# design.net
KiCad netlist of a schematic drawn in EasyEDA Pro
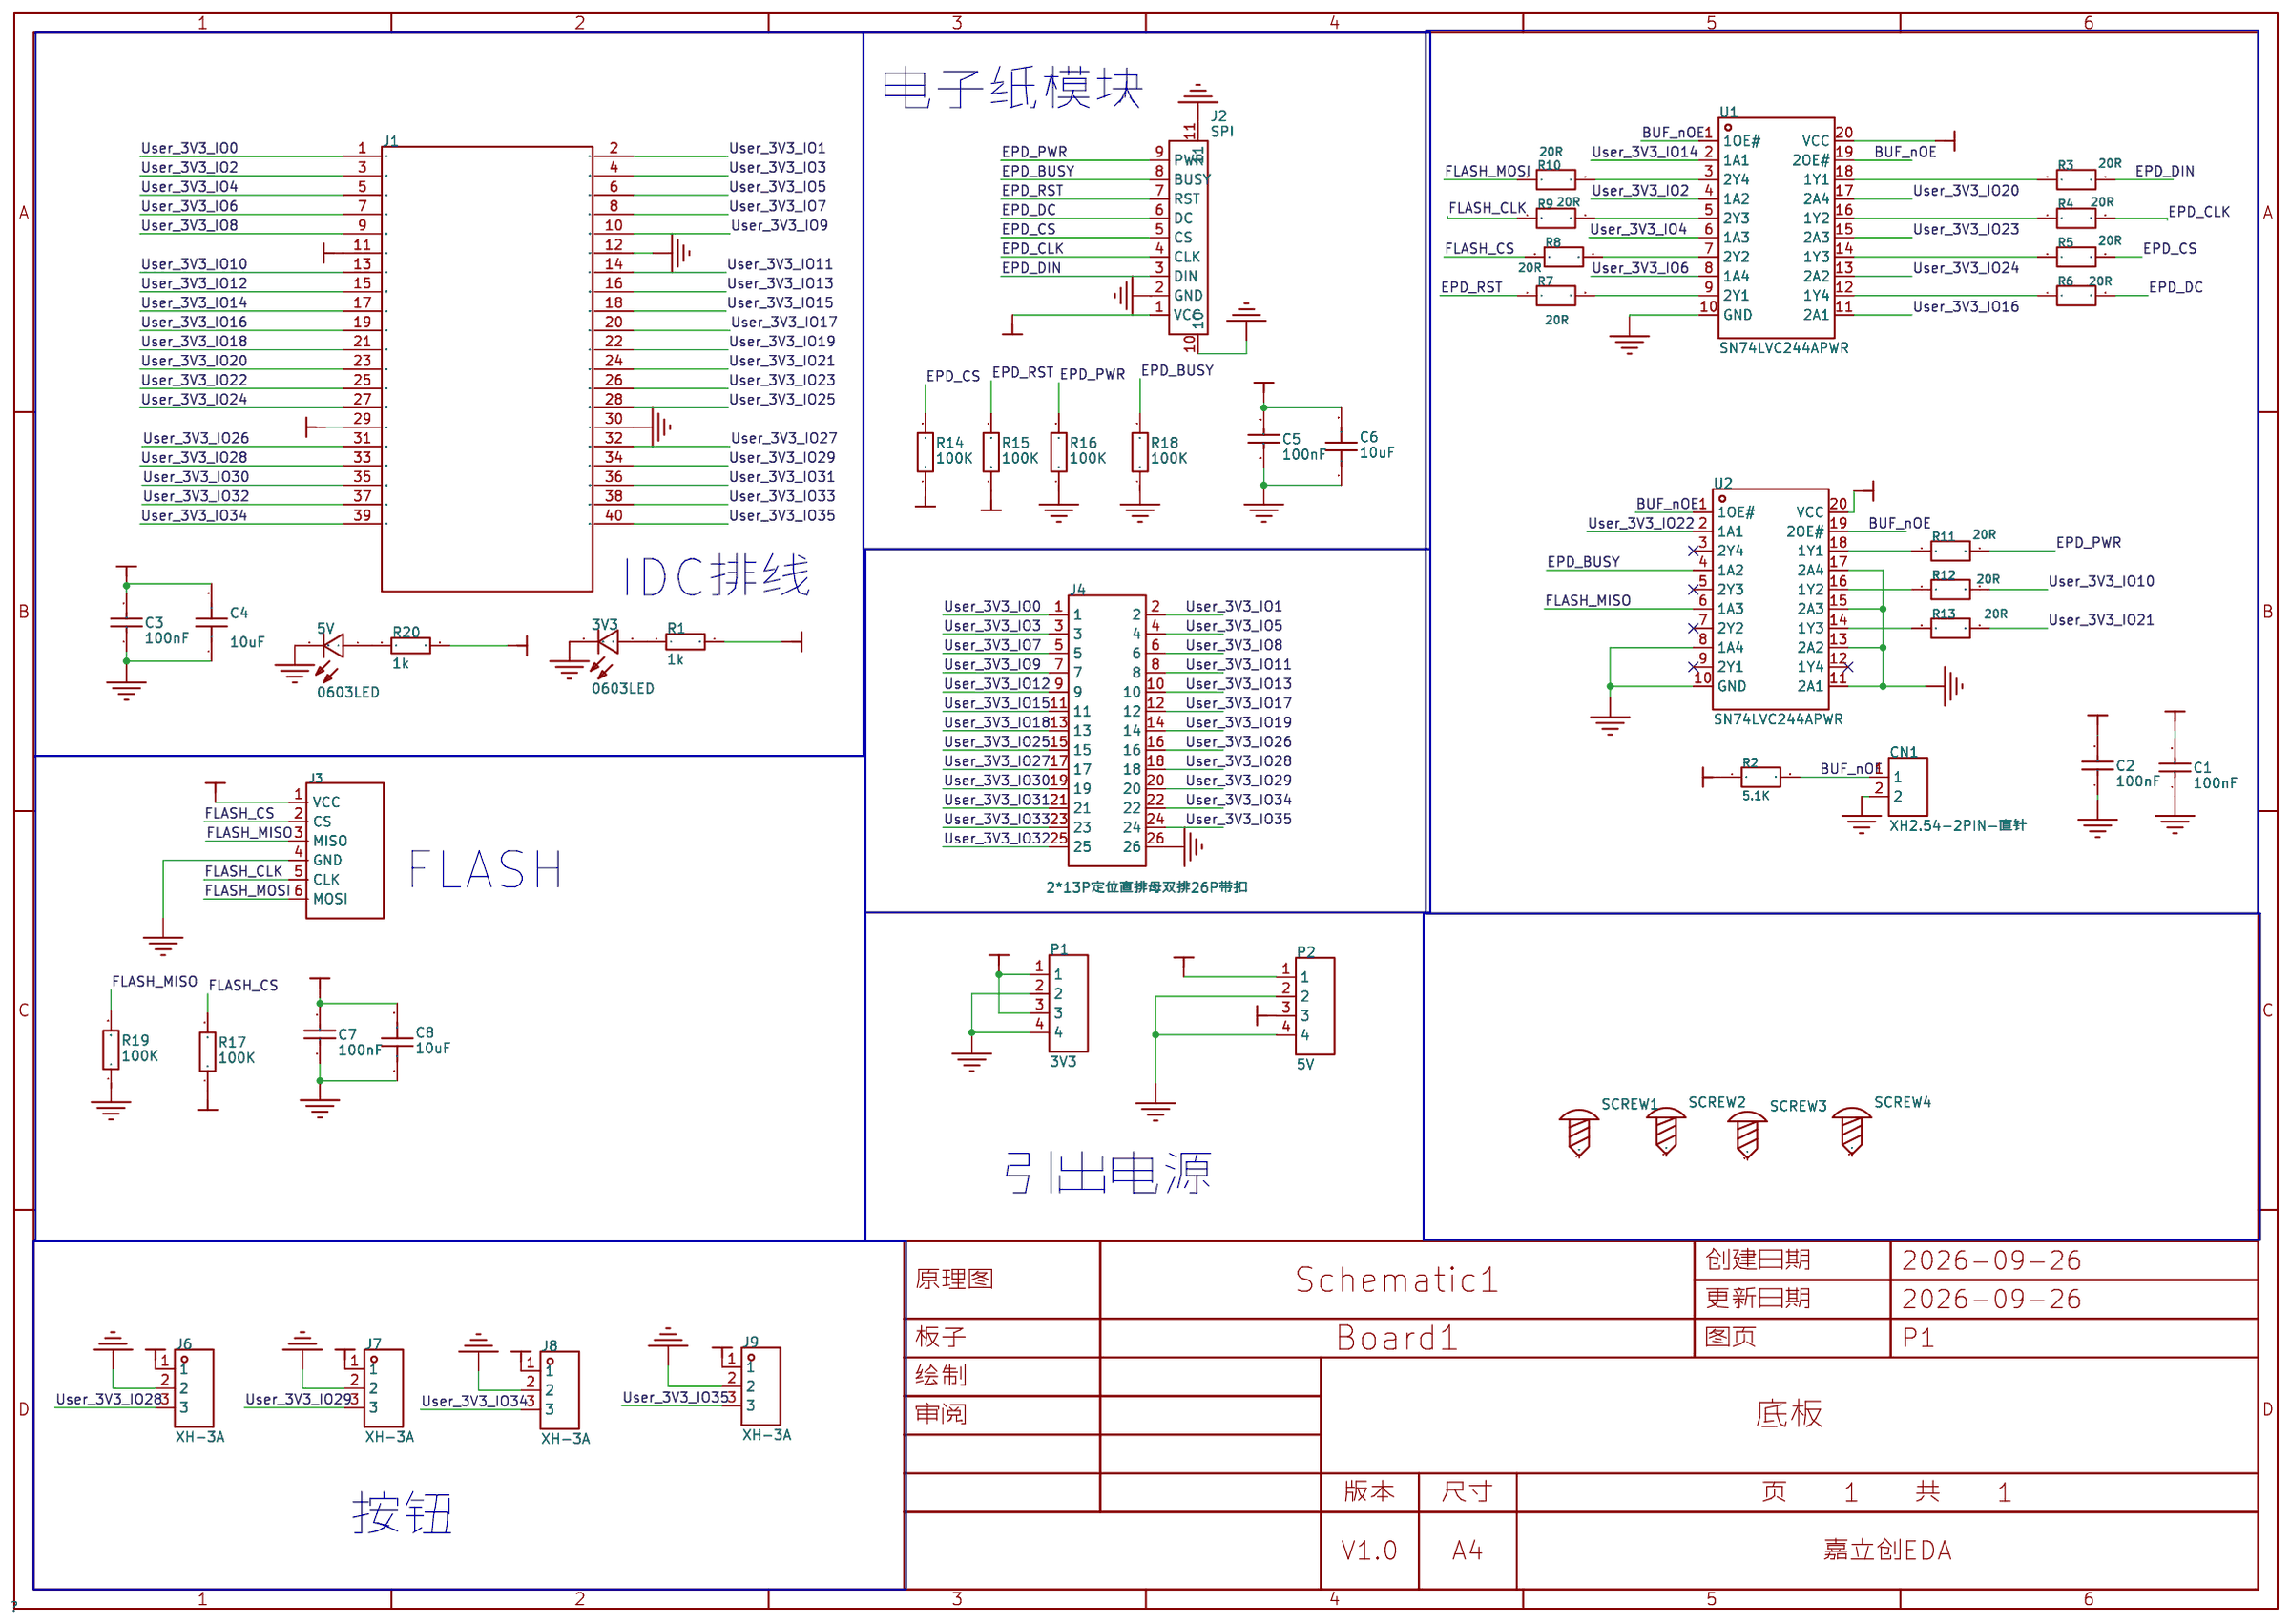
[diagram p0: schematic sheet]

(export (version "E")
  (design (tool "Eeschema 10.0.6"))
  (components
    (comp (ref "3V3")
      (value "0603LED")
      (footprint "easyedapro:LED0603-R-RD_RED")
      (libsource (lib "easyedapro") (part "0603LED"))
    )
    (comp (ref "5V")
      (value "0603LED")
      (footprint "easyedapro:LED0603-R-RD_RED")
      (libsource (lib "easyedapro") (part "0603LED"))
    )
    (comp (ref "C1")
      (value "100nF")
      (footprint "easyedapro:C0603")
      (fields
        (field (name "Manufacturer Part") "CL10A225KO8NNNC")
        (field (name "Manufacturer") "SAMSUNG(三星)")
      )
      (libsource (lib "easyedapro") (part "CL10A225KO8NNNC"))
    )
    (comp (ref "C2")
      (value "100nF")
      (footprint "easyedapro:C0603")
      (fields
        (field (name "Manufacturer Part") "CL10A225KO8NNNC")
        (field (name "Manufacturer") "SAMSUNG(三星)")
      )
      (libsource (lib "easyedapro") (part "CL10A225KO8NNNC"))
    )
    (comp (ref "C3")
      (value "100nF")
      (footprint "easyedapro:C0603")
      (fields
        (field (name "Manufacturer Part") "CL10A225KO8NNNC")
        (field (name "Manufacturer") "SAMSUNG(三星)")
      )
      (libsource (lib "easyedapro") (part "CL10A225KO8NNNC"))
    )
    (comp (ref "C4")
      (value "10uF")
      (footprint "easyedapro:C0805")
      (fields
        (field (name "Manufacturer Part") "GRM21BR61H106KE43L")
        (field (name "Manufacturer") "muRata(村田)")
      )
      (libsource (lib "easyedapro") (part "GRM21BR61H106KE43L"))
    )
    (comp (ref "C5")
      (value "100nF")
      (footprint "easyedapro:C0603")
      (fields
        (field (name "Manufacturer Part") "CL10A225KO8NNNC")
        (field (name "Manufacturer") "SAMSUNG(三星)")
      )
      (libsource (lib "easyedapro") (part "CL10A225KO8NNNC"))
    )
    (comp (ref "C6")
      (value "10uF")
      (footprint "easyedapro:C0805")
      (fields
        (field (name "Manufacturer Part") "GRM21BR61H106KE43L")
        (field (name "Manufacturer") "muRata(村田)")
      )
      (libsource (lib "easyedapro") (part "GRM21BR61H106KE43L"))
    )
    (comp (ref "C7")
      (value "100nF")
      (footprint "easyedapro:C0603")
      (fields
        (field (name "Manufacturer Part") "CL10A225KO8NNNC")
        (field (name "Manufacturer") "SAMSUNG(三星)")
      )
      (libsource (lib "easyedapro") (part "CL10A225KO8NNNC"))
    )
    (comp (ref "C8")
      (value "10uF")
      (footprint "easyedapro:C0805")
      (fields
        (field (name "Manufacturer Part") "GRM21BR61H106KE43L")
        (field (name "Manufacturer") "muRata(村田)")
      )
      (libsource (lib "easyedapro") (part "GRM21BR61H106KE43L"))
    )
    (comp (ref "CN1")
      (value "XH2.54-2PIN-直针")
      (footprint "easyedapro:CONN-TH_XH2.54-2P")
      (libsource (lib "easyedapro") (part "XH2.54-2PIN-直针"))
    )
    (comp (ref "J1")
      (value "~")
      (footprint "easyedapro:IDC40P")
      (libsource (lib "easyedapro") (part "iDC40P"))
    )
    (comp (ref "J2")
      (value "SPI")
      (footprint "easyedapro:CONN-SMD_9P-P1.25_BX-GH1.25-9PWT")
      (fields (field (name "Manufacturer") "Bossie(博锡)"))
      (libsource (lib "easyedapro") (part "BX-GH1.25-9PWT"))
    )
    (comp (ref "J3")
      (value "X4611FV-06-C63D28")
      (footprint "easyedapro:HDR-TH_6P-P2.00-V-F")
      (fields (field (name "Manufacturer") "XKB Connection(中国星坤)"))
      (libsource (lib "easyedapro") (part "X4611FV-06-C63D28"))
    )
    (comp (ref "J4")
      (value "2*13P定位直排母双排26P带扣")
      (footprint "easyedapro:IDC-TH_26P-P2.54-V-M-R2-C13-S2.54")
      (libsource (lib "easyedapro") (part "2*13P定位直排母双排26P带扣"))
    )
    (comp (ref "J6")
      (value "XH-3A")
      (footprint "easyedapro:CONN-TH_3P-P2.50_C9900023074")
      (libsource (lib "easyedapro") (part "XH-3A_C9900023074"))
    )
    (comp (ref "J7")
      (value "XH-3A")
      (footprint "easyedapro:CONN-TH_3P-P2.50_C9900023074")
      (libsource (lib "easyedapro") (part "XH-3A_C9900023074"))
    )
    (comp (ref "J8")
      (value "XH-3A")
      (footprint "easyedapro:CONN-TH_3P-P2.50_C9900023074")
      (libsource (lib "easyedapro") (part "XH-3A_C9900023074"))
    )
    (comp (ref "J9")
      (value "XH-3A")
      (footprint "easyedapro:CONN-TH_3P-P2.50_C9900023074")
      (libsource (lib "easyedapro") (part "XH-3A_C9900023074"))
    )
    (comp (ref "P1")
      (value "3V3")
      (footprint "easyedapro:CONN-TH_4P-P2.50-XH2.54-4P")
      (libsource (lib "easyedapro") (part "XH2.54-4P"))
    )
    (comp (ref "P2")
      (value "5V")
      (footprint "easyedapro:CONN-TH_4P-P2.50-XH2.54-4P")
      (libsource (lib "easyedapro") (part "XH2.54-4P"))
    )
    (comp (ref "R1")
      (value "1k")
      (footprint "easyedapro:R0603")
      (description "电阻类型:厚膜电阻;阻值:3.3kΩ;精度:±1%;功率:100mW;工作电压:75V;温度系数:±100ppm/℃;")
      (fields
        (field (name "Manufacturer Part") "0603WAF3301T5E")
        (field (name "Manufacturer") "UNI-ROYAL(厚声)")
      )
      (libsource (lib "easyedapro") (part "0603WAF3301T5E"))
    )
    (comp (ref "R2")
      (value "5.1K")
      (footprint "easyedapro:R0603")
      (fields (field (name "Manufacturer Part") "FRQ0603F1302TS") (field (name "Manufacturer") "FOJAN(富捷)"))
      (libsource (lib "easyedapro") (part "FRQ0603F1302TS"))
    )
    (comp (ref "R3")
      (value "20R")
      (footprint "easyedapro:R0603")
      (fields (field (name "Manufacturer Part") "FRQ0603F1302TS") (field (name "Manufacturer") "FOJAN(富捷)"))
      (libsource (lib "easyedapro") (part "FRQ0603F1302TS"))
    )
    (comp (ref "R4")
      (value "20R")
      (footprint "easyedapro:R0603")
      (fields (field (name "Manufacturer Part") "FRQ0603F1302TS") (field (name "Manufacturer") "FOJAN(富捷)"))
      (libsource (lib "easyedapro") (part "FRQ0603F1302TS"))
    )
    (comp (ref "R5")
      (value "20R")
      (footprint "easyedapro:R0603")
      (fields (field (name "Manufacturer Part") "FRQ0603F1302TS") (field (name "Manufacturer") "FOJAN(富捷)"))
      (libsource (lib "easyedapro") (part "FRQ0603F1302TS"))
    )
    (comp (ref "R6")
      (value "20R")
      (footprint "easyedapro:R0603")
      (fields (field (name "Manufacturer Part") "FRQ0603F1302TS") (field (name "Manufacturer") "FOJAN(富捷)"))
      (libsource (lib "easyedapro") (part "FRQ0603F1302TS"))
    )
    (comp (ref "R7")
      (value "20R")
      (footprint "easyedapro:R0603")
      (fields (field (name "Manufacturer Part") "FRQ0603F1302TS") (field (name "Manufacturer") "FOJAN(富捷)"))
      (libsource (lib "easyedapro") (part "FRQ0603F1302TS"))
    )
    (comp (ref "R8")
      (value "20R")
      (footprint "easyedapro:R0603")
      (fields (field (name "Manufacturer Part") "FRQ0603F1302TS") (field (name "Manufacturer") "FOJAN(富捷)"))
      (libsource (lib "easyedapro") (part "FRQ0603F1302TS"))
    )
    (comp (ref "R9")
      (value "20R")
      (footprint "easyedapro:R0603")
      (fields (field (name "Manufacturer Part") "FRQ0603F1302TS") (field (name "Manufacturer") "FOJAN(富捷)"))
      (libsource (lib "easyedapro") (part "FRQ0603F1302TS"))
    )
    (comp (ref "R10")
      (value "20R")
      (footprint "easyedapro:R0603")
      (fields (field (name "Manufacturer Part") "FRQ0603F1302TS") (field (name "Manufacturer") "FOJAN(富捷)"))
      (libsource (lib "easyedapro") (part "FRQ0603F1302TS"))
    )
    (comp (ref "R11")
      (value "20R")
      (footprint "easyedapro:R0603")
      (fields (field (name "Manufacturer Part") "FRQ0603F1302TS") (field (name "Manufacturer") "FOJAN(富捷)"))
      (libsource (lib "easyedapro") (part "FRQ0603F1302TS"))
    )
    (comp (ref "R12")
      (value "20R")
      (footprint "easyedapro:R0603")
      (fields (field (name "Manufacturer Part") "FRQ0603F1302TS") (field (name "Manufacturer") "FOJAN(富捷)"))
      (libsource (lib "easyedapro") (part "FRQ0603F1302TS"))
    )
    (comp (ref "R13")
      (value "20R")
      (footprint "easyedapro:R0603")
      (fields (field (name "Manufacturer Part") "FRQ0603F1302TS") (field (name "Manufacturer") "FOJAN(富捷)"))
      (libsource (lib "easyedapro") (part "FRQ0603F1302TS"))
    )
    (comp (ref "R14")
      (value "100K")
      (footprint "easyedapro:R0805")
      (fields
        (field (name "Manufacturer Part") "0805W8F3302T5E")
        (field (name "Manufacturer") "UNI-ROYAL(厚声)")
      )
      (libsource (lib "easyedapro") (part "0805W8F3302T5E"))
    )
    (comp (ref "R15")
      (value "100K")
      (footprint "easyedapro:R0805")
      (fields
        (field (name "Manufacturer Part") "0805W8F3302T5E")
        (field (name "Manufacturer") "UNI-ROYAL(厚声)")
      )
      (libsource (lib "easyedapro") (part "0805W8F3302T5E"))
    )
    (comp (ref "R16")
      (value "100K")
      (footprint "easyedapro:R0805")
      (fields
        (field (name "Manufacturer Part") "0805W8F3302T5E")
        (field (name "Manufacturer") "UNI-ROYAL(厚声)")
      )
      (libsource (lib "easyedapro") (part "0805W8F3302T5E"))
    )
    (comp (ref "R17")
      (value "100K")
      (footprint "easyedapro:R0805")
      (fields
        (field (name "Manufacturer Part") "0805W8F3302T5E")
        (field (name "Manufacturer") "UNI-ROYAL(厚声)")
      )
      (libsource (lib "easyedapro") (part "0805W8F3302T5E"))
    )
    (comp (ref "R18")
      (value "100K")
      (footprint "easyedapro:R0805")
      (fields
        (field (name "Manufacturer Part") "0805W8F3302T5E")
        (field (name "Manufacturer") "UNI-ROYAL(厚声)")
      )
      (libsource (lib "easyedapro") (part "0805W8F3302T5E"))
    )
    (comp (ref "R19")
      (value "100K")
      (footprint "easyedapro:R0805")
      (fields
        (field (name "Manufacturer Part") "0805W8F3302T5E")
        (field (name "Manufacturer") "UNI-ROYAL(厚声)")
      )
      (libsource (lib "easyedapro") (part "0805W8F3302T5E"))
    )
    (comp (ref "R20")
      (value "1k")
      (footprint "easyedapro:R0603")
      (description "电阻类型:厚膜电阻;阻值:3.3kΩ;精度:±1%;功率:100mW;工作电压:75V;温度系数:±100ppm/℃;")
      (fields
        (field (name "Manufacturer Part") "0603WAF3301T5E")
        (field (name "Manufacturer") "UNI-ROYAL(厚声)")
      )
      (libsource (lib "easyedapro") (part "0603WAF3301T5E"))
    )
    (comp (ref "SCREW1")
      (value "~")
      (footprint "easyedapro:M3螺丝")
      (libsource (lib "easyedapro") (part "螺丝孔"))
    )
    (comp (ref "SCREW2")
      (value "~")
      (footprint "easyedapro:M3螺丝")
      (libsource (lib "easyedapro") (part "螺丝孔"))
    )
    (comp (ref "SCREW3")
      (value "~")
      (footprint "easyedapro:M3螺丝")
      (libsource (lib "easyedapro") (part "螺丝孔"))
    )
    (comp (ref "SCREW4")
      (value "~")
      (footprint "easyedapro:M3螺丝")
      (libsource (lib "easyedapro") (part "螺丝孔"))
    )
    (comp (ref "U1")
      (value "SN74LVC244APWR")
      (footprint "easyedapro:TSSOP-20_L6.5-W4.4-P0.65-LS6.4-BL")
      (fields (field (name "Manufacturer") "TI(德州仪器)"))
      (libsource (lib "easyedapro") (part "SN74LVC244APWR"))
    )
    (comp (ref "U2")
      (value "SN74LVC244APWR")
      (footprint "easyedapro:TSSOP-20_L6.5-W4.4-P0.65-LS6.4-BL")
      (fields (field (name "Manufacturer") "TI(德州仪器)"))
      (libsource (lib "easyedapro") (part "SN74LVC244APWR"))
    )
  )
  (nets
    (net (code "1") (name "/BUF_nOE") (class "Default")
      (node (ref "CN1") (pin "1") (pinfunction "1_1") (pintype "unspecified"))
      (node (ref "R2") (pin "2") (pinfunction "2_2") (pintype "unspecified"))
      (node (ref "U1") (pin "1") (pinfunction "1OE#_1") (pintype "unspecified"))
      (node (ref "U1") (pin "19") (pinfunction "2OE#_19") (pintype "unspecified"))
      (node (ref "U2") (pin "1") (pinfunction "1OE#_1") (pintype "unspecified"))
      (node (ref "U2") (pin "19") (pinfunction "2OE#_19") (pintype "unspecified"))
    )
    (net (code "2") (name "/EPD_BUSY") (class "Default")
      (node (ref "J2") (pin "8") (pinfunction "BUSY_8") (pintype "unspecified"))
      (node (ref "R18") (pin "2") (pinfunction "2_2") (pintype "input"))
      (node (ref "U2") (pin "4") (pinfunction "1A2_4") (pintype "unspecified"))
    )
    (net (code "3") (name "/EPD_CLK") (class "Default")
      (node (ref "J2") (pin "4") (pinfunction "CLK_4") (pintype "unspecified"))
      (node (ref "R4") (pin "2") (pinfunction "2_2") (pintype "unspecified"))
    )
    (net (code "4") (name "/EPD_CS") (class "Default")
      (node (ref "J2") (pin "5") (pinfunction "CS_5") (pintype "unspecified"))
      (node (ref "R14") (pin "2") (pinfunction "2_2") (pintype "input"))
      (node (ref "R5") (pin "2") (pinfunction "2_2") (pintype "unspecified"))
    )
    (net (code "5") (name "/EPD_DC") (class "Default")
      (node (ref "J2") (pin "6") (pinfunction "DC_6") (pintype "unspecified"))
      (node (ref "R6") (pin "2") (pinfunction "2_2") (pintype "unspecified"))
    )
    (net (code "6") (name "/EPD_DIN") (class "Default")
      (node (ref "J2") (pin "3") (pinfunction "DIN_3") (pintype "unspecified"))
      (node (ref "R3") (pin "2") (pinfunction "2_2") (pintype "unspecified"))
    )
    (net (code "7") (name "/EPD_PWR") (class "Default")
      (node (ref "J2") (pin "9") (pinfunction "PWR_9") (pintype "unspecified"))
      (node (ref "R11") (pin "2") (pinfunction "2_2") (pintype "unspecified"))
      (node (ref "R16") (pin "2") (pinfunction "2_2") (pintype "input"))
    )
    (net (code "8") (name "/EPD_RST") (class "Default")
      (node (ref "J2") (pin "7") (pinfunction "RST_7") (pintype "unspecified"))
      (node (ref "R15") (pin "2") (pinfunction "2_2") (pintype "input"))
      (node (ref "R7") (pin "1") (pinfunction "1_1") (pintype "unspecified"))
    )
    (net (code "9") (name "/FLASH_CLK") (class "Default")
      (node (ref "J3") (pin "5") (pinfunction "CLK_5") (pintype "unspecified"))
      (node (ref "R9") (pin "1") (pinfunction "1_1") (pintype "unspecified"))
    )
    (net (code "10") (name "/FLASH_CS") (class "Default")
      (node (ref "J3") (pin "2") (pinfunction "CS_2") (pintype "unspecified"))
      (node (ref "R17") (pin "2") (pinfunction "2_2") (pintype "input"))
      (node (ref "R8") (pin "1") (pinfunction "1_1") (pintype "unspecified"))
    )
    (net (code "11") (name "/FLASH_MISO") (class "Default")
      (node (ref "J3") (pin "3") (pinfunction "MISO_3") (pintype "unspecified"))
      (node (ref "R19") (pin "2") (pinfunction "2_2") (pintype "input"))
      (node (ref "U2") (pin "6") (pinfunction "1A3_6") (pintype "unspecified"))
    )
    (net (code "12") (name "/FLASH_MOSI") (class "Default")
      (node (ref "J3") (pin "6") (pinfunction "MOSI_6") (pintype "unspecified"))
      (node (ref "R10") (pin "1") (pinfunction "1_1") (pintype "unspecified"))
    )
    (net (code "13") (name "/User_3V3_IO0") (class "Default")
      (node (ref "J1") (pin "1") (pinfunction "1_1") (pintype "unspecified"))
      (node (ref "J4") (pin "1") (pinfunction "1_1") (pintype "unspecified"))
    )
    (net (code "14") (name "/User_3V3_IO1") (class "Default")
      (node (ref "J1") (pin "2") (pinfunction "21_2") (pintype "unspecified"))
      (node (ref "J4") (pin "2") (pinfunction "2_2") (pintype "unspecified"))
    )
    (net (code "15") (name "/User_3V3_IO2") (class "Default")
      (node (ref "J1") (pin "3") (pinfunction "2_3") (pintype "unspecified"))
      (node (ref "U1") (pin "4") (pinfunction "1A2_4") (pintype "unspecified"))
    )
    (net (code "16") (name "/User_3V3_IO3") (class "Default")
      (node (ref "J1") (pin "4") (pinfunction "22_4") (pintype "unspecified"))
      (node (ref "J4") (pin "3") (pinfunction "3_3") (pintype "unspecified"))
    )
    (net (code "17") (name "/User_3V3_IO4") (class "Default")
      (node (ref "J1") (pin "5") (pinfunction "3_5") (pintype "unspecified"))
      (node (ref "U1") (pin "6") (pinfunction "1A3_6") (pintype "unspecified"))
    )
    (net (code "18") (name "/User_3V3_IO5") (class "Default")
      (node (ref "J1") (pin "6") (pinfunction "23_6") (pintype "unspecified"))
      (node (ref "J4") (pin "4") (pinfunction "4_4") (pintype "unspecified"))
    )
    (net (code "19") (name "/User_3V3_IO6") (class "Default")
      (node (ref "J1") (pin "7") (pinfunction "4_7") (pintype "unspecified"))
      (node (ref "U1") (pin "8") (pinfunction "1A4_8") (pintype "unspecified"))
    )
    (net (code "20") (name "/User_3V3_IO7") (class "Default")
      (node (ref "J1") (pin "8") (pinfunction "24_8") (pintype "unspecified"))
      (node (ref "J4") (pin "5") (pinfunction "5_5") (pintype "unspecified"))
    )
    (net (code "21") (name "/User_3V3_IO8") (class "Default")
      (node (ref "J1") (pin "9") (pinfunction "5_9") (pintype "unspecified"))
      (node (ref "J4") (pin "6") (pinfunction "6_6") (pintype "unspecified"))
    )
    (net (code "22") (name "/User_3V3_IO9") (class "Default")
      (node (ref "J1") (pin "10") (pinfunction "25_10") (pintype "unspecified"))
      (node (ref "J4") (pin "7") (pinfunction "7_7") (pintype "unspecified"))
    )
    (net (code "23") (name "/User_3V3_IO10") (class "Default")
      (node (ref "J1") (pin "13") (pinfunction "7_13") (pintype "unspecified"))
      (node (ref "R12") (pin "2") (pinfunction "2_2") (pintype "unspecified"))
    )
    (net (code "24") (name "/User_3V3_IO11") (class "Default")
      (node (ref "J1") (pin "14") (pinfunction "27_14") (pintype "unspecified"))
      (node (ref "J4") (pin "8") (pinfunction "8_8") (pintype "unspecified"))
    )
    (net (code "25") (name "/User_3V3_IO12") (class "Default")
      (node (ref "J1") (pin "15") (pinfunction "8_15") (pintype "unspecified"))
      (node (ref "J4") (pin "9") (pinfunction "9_9") (pintype "unspecified"))
    )
    (net (code "26") (name "/User_3V3_IO13") (class "Default")
      (node (ref "J1") (pin "16") (pinfunction "28_16") (pintype "unspecified"))
      (node (ref "J4") (pin "10") (pinfunction "10_10") (pintype "unspecified"))
    )
    (net (code "27") (name "/User_3V3_IO14") (class "Default")
      (node (ref "J1") (pin "17") (pinfunction "9_17") (pintype "unspecified"))
      (node (ref "U1") (pin "2") (pinfunction "1A1_2") (pintype "unspecified"))
    )
    (net (code "28") (name "/User_3V3_IO15") (class "Default")
      (node (ref "J1") (pin "18") (pinfunction "29_18") (pintype "unspecified"))
      (node (ref "J4") (pin "11") (pinfunction "11_11") (pintype "unspecified"))
    )
    (net (code "29") (name "/User_3V3_IO16") (class "Default")
      (node (ref "J1") (pin "19") (pinfunction "10_19") (pintype "unspecified"))
      (node (ref "U1") (pin "11") (pinfunction "2A1_11") (pintype "unspecified"))
    )
    (net (code "30") (name "/User_3V3_IO17") (class "Default")
      (node (ref "J1") (pin "20") (pinfunction "30_20") (pintype "unspecified"))
      (node (ref "J4") (pin "12") (pinfunction "12_12") (pintype "unspecified"))
    )
    (net (code "31") (name "/User_3V3_IO18") (class "Default")
      (node (ref "J1") (pin "21") (pinfunction "11_21") (pintype "unspecified"))
      (node (ref "J4") (pin "13") (pinfunction "13_13") (pintype "unspecified"))
    )
    (net (code "32") (name "/User_3V3_IO19") (class "Default")
      (node (ref "J1") (pin "22") (pinfunction "31_22") (pintype "unspecified"))
      (node (ref "J4") (pin "14") (pinfunction "14_14") (pintype "unspecified"))
    )
    (net (code "33") (name "/User_3V3_IO20") (class "Default")
      (node (ref "J1") (pin "23") (pinfunction "12_23") (pintype "unspecified"))
      (node (ref "U1") (pin "17") (pinfunction "2A4_17") (pintype "unspecified"))
    )
    (net (code "34") (name "/User_3V3_IO21") (class "Default")
      (node (ref "J1") (pin "24") (pinfunction "32_24") (pintype "unspecified"))
      (node (ref "R13") (pin "2") (pinfunction "2_2") (pintype "unspecified"))
    )
    (net (code "35") (name "/User_3V3_IO22") (class "Default")
      (node (ref "J1") (pin "25") (pinfunction "13_25") (pintype "unspecified"))
      (node (ref "U2") (pin "2") (pinfunction "1A1_2") (pintype "unspecified"))
    )
    (net (code "36") (name "/User_3V3_IO23") (class "Default")
      (node (ref "J1") (pin "26") (pinfunction "33_26") (pintype "unspecified"))
      (node (ref "U1") (pin "15") (pinfunction "2A3_15") (pintype "unspecified"))
    )
    (net (code "37") (name "/User_3V3_IO24") (class "Default")
      (node (ref "J1") (pin "27") (pinfunction "14_27") (pintype "unspecified"))
      (node (ref "U1") (pin "13") (pinfunction "2A2_13") (pintype "unspecified"))
    )
    (net (code "38") (name "/User_3V3_IO25") (class "Default")
      (node (ref "J1") (pin "28") (pinfunction "34_28") (pintype "unspecified"))
      (node (ref "J4") (pin "15") (pinfunction "15_15") (pintype "unspecified"))
    )
    (net (code "39") (name "/User_3V3_IO26") (class "Default")
      (node (ref "J1") (pin "31") (pinfunction "16_31") (pintype "unspecified"))
      (node (ref "J4") (pin "16") (pinfunction "16_16") (pintype "unspecified"))
    )
    (net (code "40") (name "/User_3V3_IO27") (class "Default")
      (node (ref "J1") (pin "32") (pinfunction "36_32") (pintype "unspecified"))
      (node (ref "J4") (pin "17") (pinfunction "17_17") (pintype "unspecified"))
    )
    (net (code "41") (name "/User_3V3_IO28") (class "Default")
      (node (ref "J1") (pin "33") (pinfunction "17_33") (pintype "unspecified"))
      (node (ref "J4") (pin "18") (pinfunction "18_18") (pintype "unspecified"))
      (node (ref "J6") (pin "3") (pinfunction "3_3") (pintype "unspecified"))
    )
    (net (code "42") (name "/User_3V3_IO29") (class "Default")
      (node (ref "J1") (pin "34") (pinfunction "37_34") (pintype "unspecified"))
      (node (ref "J4") (pin "20") (pinfunction "20_20") (pintype "unspecified"))
      (node (ref "J7") (pin "3") (pinfunction "3_3") (pintype "unspecified"))
    )
    (net (code "43") (name "/User_3V3_IO30") (class "Default")
      (node (ref "J1") (pin "35") (pinfunction "18_35") (pintype "unspecified"))
      (node (ref "J4") (pin "19") (pinfunction "19_19") (pintype "unspecified"))
    )
    (net (code "44") (name "/User_3V3_IO31") (class "Default")
      (node (ref "J1") (pin "36") (pinfunction "38_36") (pintype "unspecified"))
      (node (ref "J4") (pin "21") (pinfunction "21_21") (pintype "unspecified"))
    )
    (net (code "45") (name "/User_3V3_IO32") (class "Default")
      (node (ref "J1") (pin "37") (pinfunction "19_37") (pintype "unspecified"))
      (node (ref "J4") (pin "25") (pinfunction "25_25") (pintype "unspecified"))
    )
    (net (code "46") (name "/User_3V3_IO33") (class "Default")
      (node (ref "J1") (pin "38") (pinfunction "39_38") (pintype "unspecified"))
      (node (ref "J4") (pin "23") (pinfunction "23_23") (pintype "unspecified"))
    )
    (net (code "47") (name "/User_3V3_IO34") (class "Default")
      (node (ref "J1") (pin "39") (pinfunction "20_39") (pintype "unspecified"))
      (node (ref "J4") (pin "22") (pinfunction "22_22") (pintype "unspecified"))
      (node (ref "J8") (pin "3") (pinfunction "3_3") (pintype "unspecified"))
    )
    (net (code "48") (name "/User_3V3_IO35") (class "Default")
      (node (ref "J1") (pin "40") (pinfunction "40_40") (pintype "unspecified"))
      (node (ref "J4") (pin "24") (pinfunction "24_24") (pintype "unspecified"))
      (node (ref "J9") (pin "3") (pinfunction "3_3") (pintype "unspecified"))
    )
    (net (code "49") (name "3V3") (class "Default")
      (node (ref "C1") (pin "2") (pinfunction "2_2") (pintype "input"))
      (node (ref "C2") (pin "2") (pinfunction "2_2") (pintype "input"))
      (node (ref "C3") (pin "2") (pinfunction "2_2") (pintype "input"))
      (node (ref "C4") (pin "2") (pinfunction "2_2") (pintype "unspecified"))
      (node (ref "C5") (pin "2") (pinfunction "2_2") (pintype "input"))
      (node (ref "C6") (pin "2") (pinfunction "2_2") (pintype "unspecified"))
      (node (ref "C7") (pin "2") (pinfunction "2_2") (pintype "input"))
      (node (ref "C8") (pin "2") (pinfunction "2_2") (pintype "unspecified"))
      (node (ref "J1") (pin "29") (pinfunction "15_29") (pintype "unspecified"))
      (node (ref "J2") (pin "1") (pinfunction "VCC_1") (pintype "unspecified"))
      (node (ref "J3") (pin "1") (pinfunction "VCC_1") (pintype "unspecified"))
      (node (ref "J6") (pin "1") (pinfunction "1_1") (pintype "unspecified"))
      (node (ref "J7") (pin "1") (pinfunction "1_1") (pintype "unspecified"))
      (node (ref "J8") (pin "1") (pinfunction "1_1") (pintype "unspecified"))
      (node (ref "J9") (pin "1") (pinfunction "1_1") (pintype "unspecified"))
      (node (ref "P1") (pin "1") (pinfunction "1_1") (pintype "unspecified"))
      (node (ref "P1") (pin "3") (pinfunction "3_3") (pintype "unspecified"))
      (node (ref "R1") (pin "2") (pinfunction "2_2") (pintype "input"))
      (node (ref "R14") (pin "1") (pinfunction "1_1") (pintype "input"))
      (node (ref "R15") (pin "1") (pinfunction "1_1") (pintype "input"))
      (node (ref "R17") (pin "1") (pinfunction "1_1") (pintype "input"))
      (node (ref "R2") (pin "1") (pinfunction "1_1") (pintype "unspecified"))
      (node (ref "U1") (pin "20") (pinfunction "VCC_20") (pintype "unspecified"))
      (node (ref "U2") (pin "20") (pinfunction "VCC_20") (pintype "unspecified"))
    )
    (net (code "50") (name "5V") (class "Default")
      (node (ref "J1") (pin "11") (pinfunction "6_11") (pintype "unspecified"))
      (node (ref "R20") (pin "2") (pinfunction "2_2") (pintype "input"))
    )
    (net (code "51") (name "GND") (class "Default")
      (node (ref "3V3") (pin "2") (pinfunction "C_2") (pintype "input"))
      (node (ref "5V") (pin "2") (pinfunction "C_2") (pintype "input"))
      (node (ref "C1") (pin "1") (pinfunction "1_1") (pintype "input"))
      (node (ref "C2") (pin "1") (pinfunction "1_1") (pintype "input"))
      (node (ref "C3") (pin "1") (pinfunction "1_1") (pintype "input"))
      (node (ref "C4") (pin "1") (pinfunction "1_1") (pintype "unspecified"))
      (node (ref "C5") (pin "1") (pinfunction "1_1") (pintype "input"))
      (node (ref "C6") (pin "1") (pinfunction "1_1") (pintype "unspecified"))
      (node (ref "C7") (pin "1") (pinfunction "1_1") (pintype "input"))
      (node (ref "C8") (pin "1") (pinfunction "1_1") (pintype "unspecified"))
      (node (ref "CN1") (pin "2") (pinfunction "2_2") (pintype "unspecified"))
      (node (ref "J1") (pin "12") (pinfunction "26_12") (pintype "unspecified"))
      (node (ref "J1") (pin "30") (pinfunction "35_30") (pintype "unspecified"))
      (node (ref "J2") (pin "10") (pinfunction "10_10") (pintype "unspecified"))
      (node (ref "J2") (pin "11") (pinfunction "11_11") (pintype "unspecified"))
      (node (ref "J2") (pin "2") (pinfunction "GND_2") (pintype "unspecified"))
      (node (ref "J3") (pin "4") (pinfunction "GND_4") (pintype "unspecified"))
      (node (ref "J4") (pin "26") (pinfunction "26_26") (pintype "unspecified"))
      (node (ref "J6") (pin "2") (pinfunction "2_2") (pintype "unspecified"))
      (node (ref "J7") (pin "2") (pinfunction "2_2") (pintype "unspecified"))
      (node (ref "J8") (pin "2") (pinfunction "2_2") (pintype "unspecified"))
      (node (ref "J9") (pin "2") (pinfunction "2_2") (pintype "unspecified"))
      (node (ref "P1") (pin "2") (pinfunction "2_2") (pintype "unspecified"))
      (node (ref "P1") (pin "4") (pinfunction "4_4") (pintype "unspecified"))
      (node (ref "P2") (pin "2") (pinfunction "2_2") (pintype "unspecified"))
      (node (ref "R16") (pin "1") (pinfunction "1_1") (pintype "input"))
      (node (ref "R18") (pin "1") (pinfunction "1_1") (pintype "input"))
      (node (ref "R19") (pin "1") (pinfunction "1_1") (pintype "input"))
      (node (ref "U1") (pin "10") (pinfunction "GND_10") (pintype "unspecified"))
      (node (ref "U2") (pin "10") (pinfunction "GND_10") (pintype "unspecified"))
      (node (ref "U2") (pin "11") (pinfunction "2A1_11") (pintype "unspecified"))
      (node (ref "U2") (pin "13") (pinfunction "2A2_13") (pintype "unspecified"))
      (node (ref "U2") (pin "15") (pinfunction "2A3_15") (pintype "unspecified"))
      (node (ref "U2") (pin "17") (pinfunction "2A4_17") (pintype "unspecified"))
      (node (ref "U2") (pin "8") (pinfunction "1A4_8") (pintype "unspecified"))
    )
    (net (code "52") (name "Net-(3V3-A)") (class "Default")
      (node (ref "3V3") (pin "1") (pinfunction "A_1") (pintype "input"))
      (node (ref "R1") (pin "1") (pinfunction "1_1") (pintype "input"))
    )
    (net (code "53") (name "Net-(5V-A)") (class "Default")
      (node (ref "5V") (pin "1") (pinfunction "A_1") (pintype "input"))
      (node (ref "R20") (pin "1") (pinfunction "1_1") (pintype "input"))
    )
    (net (code "54") (name "Net-(U1-1Y1)") (class "Default")
      (node (ref "R3") (pin "1") (pinfunction "1_1") (pintype "unspecified"))
      (node (ref "U1") (pin "18") (pinfunction "1Y1_18") (pintype "unspecified"))
    )
    (net (code "55") (name "Net-(U1-1Y2)") (class "Default")
      (node (ref "R4") (pin "1") (pinfunction "1_1") (pintype "unspecified"))
      (node (ref "U1") (pin "16") (pinfunction "1Y2_16") (pintype "unspecified"))
    )
    (net (code "56") (name "Net-(U1-1Y3)") (class "Default")
      (node (ref "R5") (pin "1") (pinfunction "1_1") (pintype "unspecified"))
      (node (ref "U1") (pin "14") (pinfunction "1Y3_14") (pintype "unspecified"))
    )
    (net (code "57") (name "Net-(U1-1Y4)") (class "Default")
      (node (ref "R6") (pin "1") (pinfunction "1_1") (pintype "unspecified"))
      (node (ref "U1") (pin "12") (pinfunction "1Y4_12") (pintype "unspecified"))
    )
    (net (code "58") (name "Net-(U1-2Y1)") (class "Default")
      (node (ref "R7") (pin "2") (pinfunction "2_2") (pintype "unspecified"))
      (node (ref "U1") (pin "9") (pinfunction "2Y1_9") (pintype "unspecified"))
    )
    (net (code "59") (name "Net-(U1-2Y2)") (class "Default")
      (node (ref "R8") (pin "2") (pinfunction "2_2") (pintype "unspecified"))
      (node (ref "U1") (pin "7") (pinfunction "2Y2_7") (pintype "unspecified"))
    )
    (net (code "60") (name "Net-(U1-2Y3)") (class "Default")
      (node (ref "R9") (pin "2") (pinfunction "2_2") (pintype "unspecified"))
      (node (ref "U1") (pin "5") (pinfunction "2Y3_5") (pintype "unspecified"))
    )
    (net (code "61") (name "Net-(U1-2Y4)") (class "Default")
      (node (ref "R10") (pin "2") (pinfunction "2_2") (pintype "unspecified"))
      (node (ref "U1") (pin "3") (pinfunction "2Y4_3") (pintype "unspecified"))
    )
    (net (code "62") (name "Net-(U2-1Y1)") (class "Default")
      (node (ref "R11") (pin "1") (pinfunction "1_1") (pintype "unspecified"))
      (node (ref "U2") (pin "18") (pinfunction "1Y1_18") (pintype "unspecified"))
    )
    (net (code "63") (name "Net-(U2-1Y2)") (class "Default")
      (node (ref "R12") (pin "1") (pinfunction "1_1") (pintype "unspecified"))
      (node (ref "U2") (pin "16") (pinfunction "1Y2_16") (pintype "unspecified"))
    )
    (net (code "64") (name "Net-(U2-1Y3)") (class "Default")
      (node (ref "R13") (pin "1") (pinfunction "1_1") (pintype "unspecified"))
      (node (ref "U2") (pin "14") (pinfunction "1Y3_14") (pintype "unspecified"))
    )
    (net (code "65") (name "unconnected-(P2-Pad1)") (class "Default")
      (node (ref "P2") (pin "1") (pinfunction "1_1") (pintype "unspecified"))
    )
    (net (code "66") (name "unconnected-(P2-Pad3)") (class "Default")
      (node (ref "P2") (pin "3") (pinfunction "3_3") (pintype "unspecified"))
    )
    (net (code "67") (name "unconnected-(P2-Pad4)") (class "Default")
      (node (ref "P2") (pin "4") (pinfunction "4_4") (pintype "unspecified"))
    )
    (net (code "68") (name "unconnected-(SCREW1-Pad1)") (class "Default")
      (node (ref "SCREW1") (pin "1") (pinfunction "1_1") (pintype "input"))
    )
    (net (code "69") (name "unconnected-(SCREW2-Pad1)") (class "Default")
      (node (ref "SCREW2") (pin "1") (pinfunction "1_1") (pintype "input"))
    )
    (net (code "70") (name "unconnected-(SCREW3-Pad1)") (class "Default")
      (node (ref "SCREW3") (pin "1") (pinfunction "1_1") (pintype "input"))
    )
    (net (code "71") (name "unconnected-(SCREW4-Pad1)") (class "Default")
      (node (ref "SCREW4") (pin "1") (pinfunction "1_1") (pintype "input"))
    )
    (net (code "72") (name "unconnected-(U2-1Y4-Pad12)") (class "Default")
      (node (ref "U2") (pin "12") (pinfunction "1Y4_12") (pintype "unspecified+no_connect"))
    )
    (net (code "73") (name "unconnected-(U2-2Y1-Pad9)") (class "Default")
      (node (ref "U2") (pin "9") (pinfunction "2Y1_9") (pintype "unspecified+no_connect"))
    )
    (net (code "74") (name "unconnected-(U2-2Y2-Pad7)") (class "Default")
      (node (ref "U2") (pin "7") (pinfunction "2Y2_7") (pintype "unspecified+no_connect"))
    )
    (net (code "75") (name "unconnected-(U2-2Y3-Pad5)") (class "Default")
      (node (ref "U2") (pin "5") (pinfunction "2Y3_5") (pintype "unspecified+no_connect"))
    )
    (net (code "76") (name "unconnected-(U2-2Y4-Pad3)") (class "Default")
      (node (ref "U2") (pin "3") (pinfunction "2Y4_3") (pintype "unspecified+no_connect"))
    )
  )
)
